# BPF_eval_R2.net
KiCad netlist of a schematic drawn in EAGLE
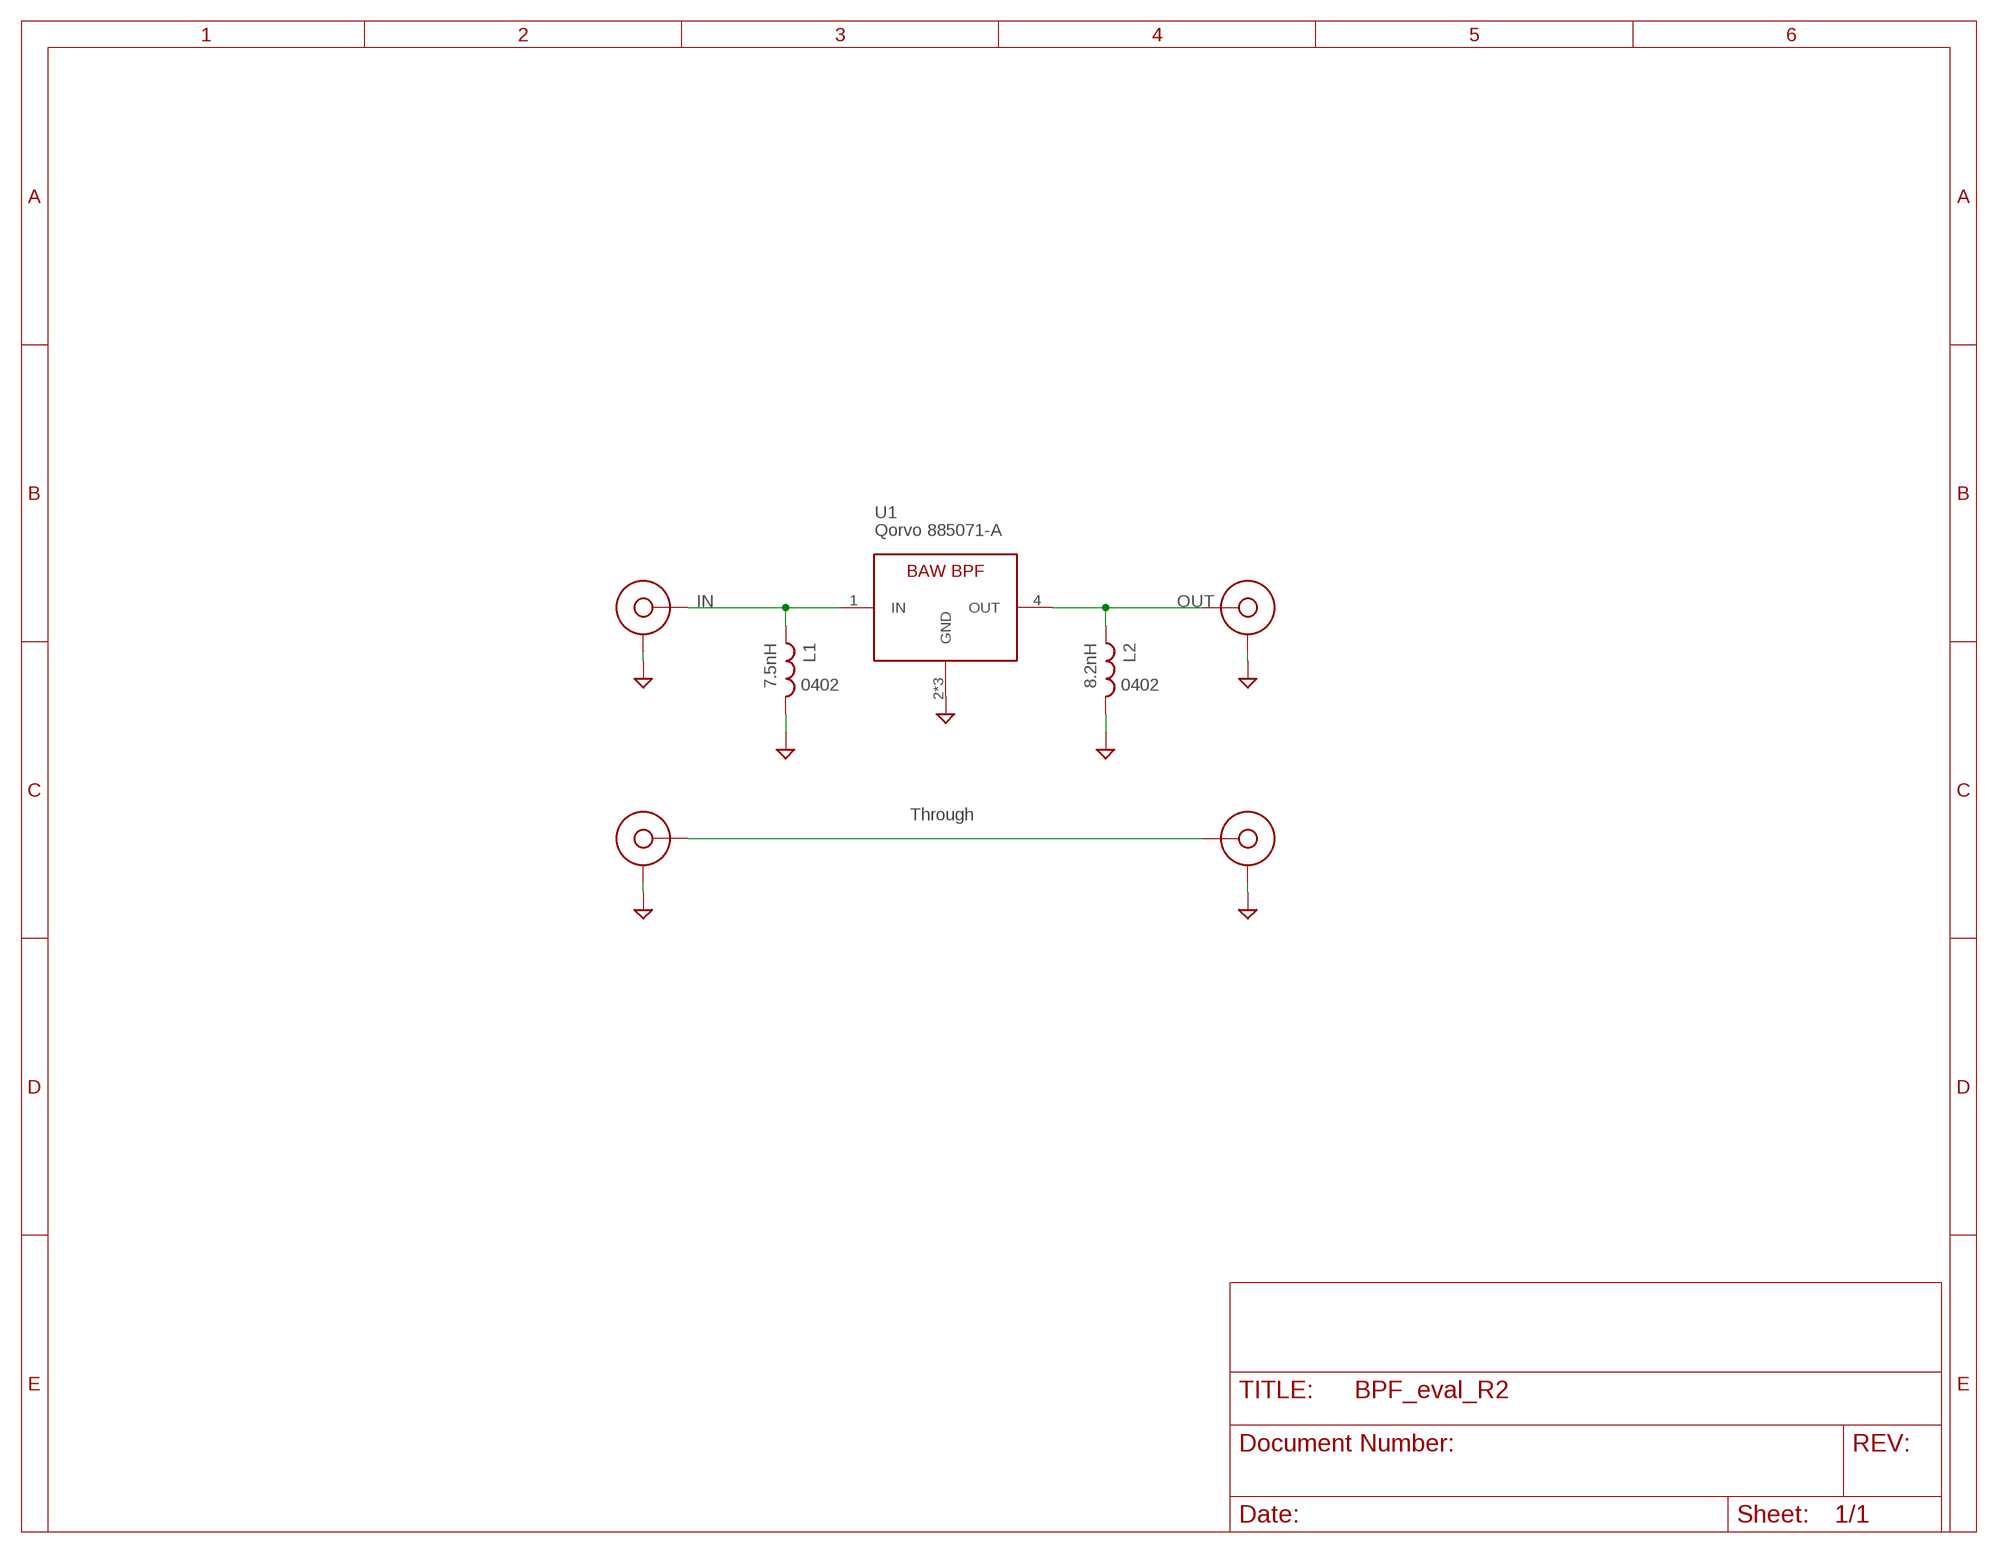
[diagram p0: schematic, sheet 1]

(export (version "E")
  (design (tool "Eeschema 10.0.6"))
  (components
    (comp (ref "CF1")
      (value "SMA-CINCH-END-FIRE")
      (footprint "eagle-import:SMAJ716-ND")
      (libsource (lib "eagle-import") (part "SMA-CINCH-END-FIRE"))
    )
    (comp (ref "CF2")
      (value "SMA-CINCH-END-FIRE")
      (footprint "eagle-import:SMAJ716-ND")
      (libsource (lib "eagle-import") (part "SMA-CINCH-END-FIRE"))
    )
    (comp (ref "CF3")
      (value "SMA-CINCH-END-FIRE")
      (footprint "eagle-import:SMAJ716-ND")
      (libsource (lib "eagle-import") (part "SMA-CINCH-END-FIRE"))
    )
    (comp (ref "CF4")
      (value "SMA-CINCH-END-FIRE")
      (footprint "eagle-import:SMAJ716-ND")
      (libsource (lib "eagle-import") (part "SMA-CINCH-END-FIRE"))
    )
    (comp (ref "L1")
      (value "7.5nH")
      (footprint "eagle-import:.0402-B-NOSILK")
      (libsource (lib "eagle-import") (part "L-US0402-B-NOSILK"))
    )
    (comp (ref "L2")
      (value "8.2nH")
      (footprint "eagle-import:.0402-B-NOSILK")
      (libsource (lib "eagle-import") (part "L-US0402-B-NOSILK"))
    )
    (comp (ref "U1")
      (value "885071-A")
      (footprint "eagle-import:FIL_B39162B9417K610")
      (libsource (lib "eagle-import") (part "885071-A"))
    )
  )
  (nets
    (net (code "1") (name "/IN") (class "Default")
      (node (ref "CF1") (pin "P$3") (pinfunction "CENTERCONDUCTOR_P$3") (pintype "bidirectional"))
      (node (ref "L1") (pin "1") (pinfunction "1_1") (pintype "passive"))
      (node (ref "U1") (pin "1") (pinfunction "IN_1") (pintype "passive"))
    )
    (net (code "2") (name "/OUT") (class "Default")
      (node (ref "CF3") (pin "P$3") (pinfunction "CENTERCONDUCTOR_P$3") (pintype "bidirectional"))
      (node (ref "L2") (pin "1") (pinfunction "1_1") (pintype "passive"))
      (node (ref "U1") (pin "4") (pinfunction "OUT_4") (pintype "passive"))
    )
    (net (code "3") (name "GND") (class "Default")
      (node (ref "CF1") (pin "GND1") (pinfunction "GND_GND1") (pintype "power_in"))
      (node (ref "CF1") (pin "GND2") (pinfunction "GND_GND2") (pintype "power_in"))
      (node (ref "CF1") (pin "GND3") (pinfunction "GND_GND3") (pintype "power_in"))
      (node (ref "CF1") (pin "GND4") (pinfunction "GND_GND4") (pintype "power_in"))
      (node (ref "CF2") (pin "GND1") (pinfunction "GND_GND1") (pintype "power_in"))
      (node (ref "CF2") (pin "GND2") (pinfunction "GND_GND2") (pintype "power_in"))
      (node (ref "CF2") (pin "GND3") (pinfunction "GND_GND3") (pintype "power_in"))
      (node (ref "CF2") (pin "GND4") (pinfunction "GND_GND4") (pintype "power_in"))
      (node (ref "CF3") (pin "GND1") (pinfunction "GND_GND1") (pintype "power_in"))
      (node (ref "CF3") (pin "GND2") (pinfunction "GND_GND2") (pintype "power_in"))
      (node (ref "CF3") (pin "GND3") (pinfunction "GND_GND3") (pintype "power_in"))
      (node (ref "CF3") (pin "GND4") (pinfunction "GND_GND4") (pintype "power_in"))
      (node (ref "CF4") (pin "GND1") (pinfunction "GND_GND1") (pintype "power_in"))
      (node (ref "CF4") (pin "GND2") (pinfunction "GND_GND2") (pintype "power_in"))
      (node (ref "CF4") (pin "GND3") (pinfunction "GND_GND3") (pintype "power_in"))
      (node (ref "CF4") (pin "GND4") (pinfunction "GND_GND4") (pintype "power_in"))
      (node (ref "L1") (pin "2") (pinfunction "2_2") (pintype "passive"))
      (node (ref "L2") (pin "2") (pinfunction "2_2") (pintype "passive"))
      (node (ref "U1") (pin "2") (pinfunction "GND_2") (pintype "power_in"))
      (node (ref "U1") (pin "3") (pinfunction "GND_3") (pintype "power_in"))
      (node (ref "U1") (pin "5") (pinfunction "GND_5") (pintype "power_in"))
    )
    (net (code "4") (name "Net-(CF2-CENTERCONDUCTOR)") (class "Default")
      (node (ref "CF2") (pin "P$3") (pinfunction "CENTERCONDUCTOR_P$3") (pintype "bidirectional"))
      (node (ref "CF4") (pin "P$3") (pinfunction "CENTERCONDUCTOR_P$3") (pintype "bidirectional"))
    )
  )
)
